# PowerBar.net
KiCad netlist of a schematic drawn in EAGLE
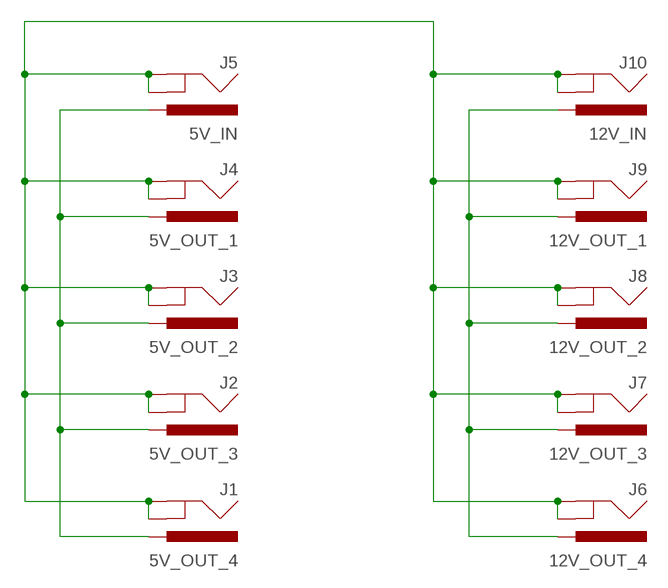
[diagram p0: schematic, sheet 1]

(export (version "E")
  (design (tool "Eeschema 10.0.6"))
  (components
    (comp (ref "J1")
      (value "5V_OUT_4")
      (footprint "eagle-import:POWER_JACK_PTH")
      (libsource (lib "eagle-import") (part "POWER_JACKPTH"))
    )
    (comp (ref "J2")
      (value "5V_OUT_3")
      (footprint "eagle-import:POWER_JACK_PTH")
      (libsource (lib "eagle-import") (part "POWER_JACKPTH"))
    )
    (comp (ref "J3")
      (value "5V_OUT_2")
      (footprint "eagle-import:POWER_JACK_PTH")
      (libsource (lib "eagle-import") (part "POWER_JACKPTH"))
    )
    (comp (ref "J4")
      (value "5V_OUT_1")
      (footprint "eagle-import:POWER_JACK_PTH")
      (libsource (lib "eagle-import") (part "POWER_JACKPTH"))
    )
    (comp (ref "J5")
      (value "5V_IN")
      (footprint "eagle-import:POWER_JACK_PTH")
      (libsource (lib "eagle-import") (part "POWER_JACKPTH"))
    )
    (comp (ref "J6")
      (value "12V_OUT_4")
      (footprint "eagle-import:POWER_JACK_PTH")
      (libsource (lib "eagle-import") (part "POWER_JACKPTH"))
    )
    (comp (ref "J7")
      (value "12V_OUT_3")
      (footprint "eagle-import:POWER_JACK_PTH")
      (libsource (lib "eagle-import") (part "POWER_JACKPTH"))
    )
    (comp (ref "J8")
      (value "12V_OUT_2")
      (footprint "eagle-import:POWER_JACK_PTH")
      (libsource (lib "eagle-import") (part "POWER_JACKPTH"))
    )
    (comp (ref "J9")
      (value "12V_OUT_1")
      (footprint "eagle-import:POWER_JACK_PTH")
      (libsource (lib "eagle-import") (part "POWER_JACKPTH"))
    )
    (comp (ref "J10")
      (value "12V_IN")
      (footprint "eagle-import:POWER_JACK_PTH")
      (libsource (lib "eagle-import") (part "POWER_JACKPTH"))
    )
  )
  (nets
    (net (code "1") (name "Net-(J1-PadGND)") (class "Default")
      (node (ref "J1") (pin "GND") (pinfunction "GND_GND") (pintype "bidirectional"))
      (node (ref "J1") (pin "GNDBREAK") (pinfunction "GNDBREAK_GNDBREAK") (pintype "bidirectional"))
      (node (ref "J10") (pin "GND") (pinfunction "GND_GND") (pintype "bidirectional"))
      (node (ref "J10") (pin "GNDBREAK") (pinfunction "GNDBREAK_GNDBREAK") (pintype "bidirectional"))
      (node (ref "J2") (pin "GND") (pinfunction "GND_GND") (pintype "bidirectional"))
      (node (ref "J2") (pin "GNDBREAK") (pinfunction "GNDBREAK_GNDBREAK") (pintype "bidirectional"))
      (node (ref "J3") (pin "GND") (pinfunction "GND_GND") (pintype "bidirectional"))
      (node (ref "J3") (pin "GNDBREAK") (pinfunction "GNDBREAK_GNDBREAK") (pintype "bidirectional"))
      (node (ref "J4") (pin "GND") (pinfunction "GND_GND") (pintype "bidirectional"))
      (node (ref "J4") (pin "GNDBREAK") (pinfunction "GNDBREAK_GNDBREAK") (pintype "bidirectional"))
      (node (ref "J5") (pin "GND") (pinfunction "GND_GND") (pintype "bidirectional"))
      (node (ref "J5") (pin "GNDBREAK") (pinfunction "GNDBREAK_GNDBREAK") (pintype "bidirectional"))
      (node (ref "J6") (pin "GND") (pinfunction "GND_GND") (pintype "bidirectional"))
      (node (ref "J6") (pin "GNDBREAK") (pinfunction "GNDBREAK_GNDBREAK") (pintype "bidirectional"))
      (node (ref "J7") (pin "GND") (pinfunction "GND_GND") (pintype "bidirectional"))
      (node (ref "J7") (pin "GNDBREAK") (pinfunction "GNDBREAK_GNDBREAK") (pintype "bidirectional"))
      (node (ref "J8") (pin "GND") (pinfunction "GND_GND") (pintype "bidirectional"))
      (node (ref "J8") (pin "GNDBREAK") (pinfunction "GNDBREAK_GNDBREAK") (pintype "bidirectional"))
      (node (ref "J9") (pin "GND") (pinfunction "GND_GND") (pintype "bidirectional"))
      (node (ref "J9") (pin "GNDBREAK") (pinfunction "GNDBREAK_GNDBREAK") (pintype "bidirectional"))
    )
    (net (code "2") (name "Net-(J1-PadPWR)") (class "Default")
      (node (ref "J1") (pin "PWR") (pinfunction "PWR_PWR") (pintype "bidirectional"))
      (node (ref "J2") (pin "PWR") (pinfunction "PWR_PWR") (pintype "bidirectional"))
      (node (ref "J3") (pin "PWR") (pinfunction "PWR_PWR") (pintype "bidirectional"))
      (node (ref "J4") (pin "PWR") (pinfunction "PWR_PWR") (pintype "bidirectional"))
      (node (ref "J5") (pin "PWR") (pinfunction "PWR_PWR") (pintype "bidirectional"))
    )
    (net (code "3") (name "Net-(J10-PadPWR)") (class "Default")
      (node (ref "J10") (pin "PWR") (pinfunction "PWR_PWR") (pintype "bidirectional"))
      (node (ref "J6") (pin "PWR") (pinfunction "PWR_PWR") (pintype "bidirectional"))
      (node (ref "J7") (pin "PWR") (pinfunction "PWR_PWR") (pintype "bidirectional"))
      (node (ref "J8") (pin "PWR") (pinfunction "PWR_PWR") (pintype "bidirectional"))
      (node (ref "J9") (pin "PWR") (pinfunction "PWR_PWR") (pintype "bidirectional"))
    )
  )
)
